# 51-2001-01-18_04_Power_Module_Schematic.net
KiCad netlist of a schematic drawn in Altium Designer
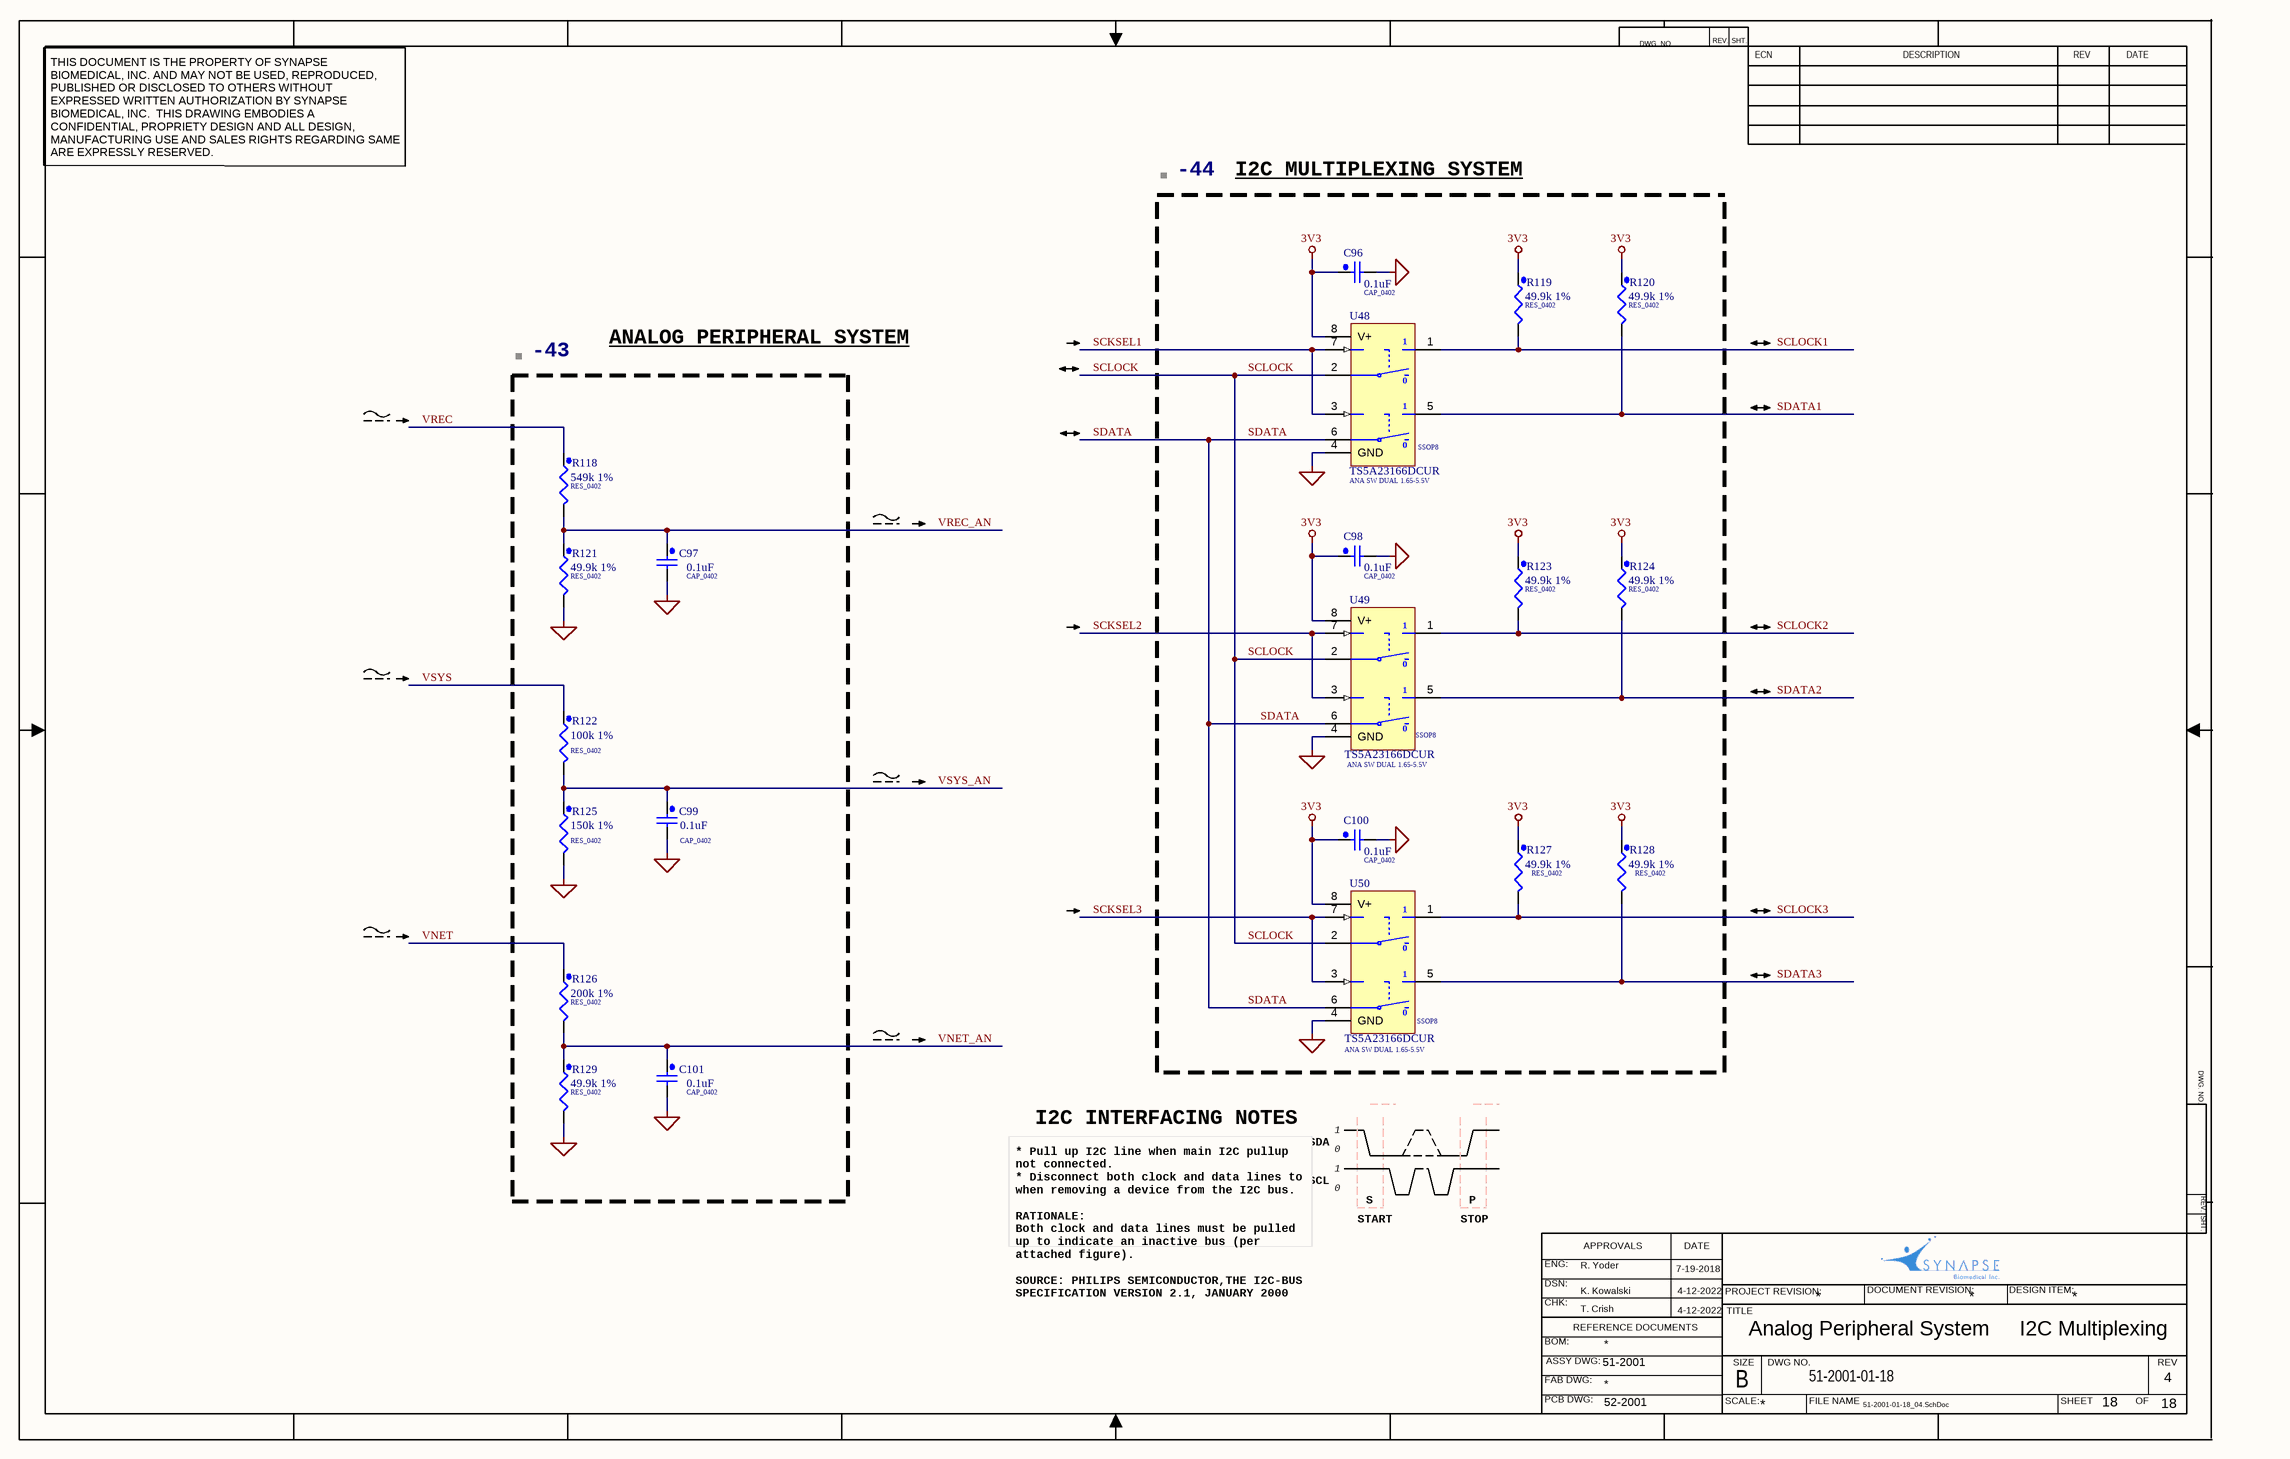
[diagram p0: 51-2001-01-18_04 Power Module Schematic.SchDoc]

(export (version "E")
  (design (tool "Eeschema 10.0.6"))
  (components
    (comp (ref "-43")
      (value "BOM_S1")
      (description "BOM item small graphic")
      (fields (field (name "XDESCRIPTION") "ANALOG PERIPHERAL SYSTEM"))
      (libsource (lib "BOM_sym") (part "BOM_S1"))
    )
    (comp (ref "-44")
      (value "BOM_S1")
      (description "BOM item small graphic")
      (fields (field (name "XDESCRIPTION") "I2C MULTIPLEXING SYSTEM"))
      (libsource (lib "BOM_sym") (part "BOM_S1"))
    )
    (comp (ref "C96")
      (value "0.1uF")
      (footprint "CAP_0402")
      (description "0.1uF, 16V, X7R, 0402, RoHS")
      (fields
        (field (name "MFR") "Murata")
        (field (name "PACKAGEDESCRIPTION") "CAP_0402")
        (field (name "MPN") "GRM155R71C104KA88D")
      )
      (libsource (lib "NNPS Integrated Parts") (part "GRM155R71C104KA88D"))
    )
    (comp (ref "C97")
      (value "0.1uF")
      (footprint "CAP_0402")
      (description "0.1uF, 16V, X7R, 0402, RoHS")
      (fields
        (field (name "MFR") "Murata")
        (field (name "PACKAGEDESCRIPTION") "CAP_0402")
        (field (name "MPN") "GRM155R71C104KA88D")
      )
      (libsource (lib "NNPS Integrated Parts") (part "GRM155R71C104KA88D"))
    )
    (comp (ref "C98")
      (value "0.1uF")
      (footprint "CAP_0402")
      (description "0.1uF, 16V, X7R, 0402, RoHS")
      (fields
        (field (name "MFR") "Murata")
        (field (name "PACKAGEDESCRIPTION") "CAP_0402")
        (field (name "MPN") "GRM155R71C104KA88D")
      )
      (libsource (lib "NNPS Integrated Parts") (part "GRM155R71C104KA88D"))
    )
    (comp (ref "C99")
      (value "0.1uF")
      (footprint "CAP_0402")
      (description "0.1uF, 16V, X7R, 0402, RoHS")
      (fields
        (field (name "MFR") "Murata")
        (field (name "PACKAGEDESCRIPTION") "CAP_0402")
        (field (name "MPN") "GRM155R71C104KA88D")
      )
      (libsource (lib "NNPS Integrated Parts") (part "GRM155R71C104KA88D"))
    )
    (comp (ref "C100")
      (value "0.1uF")
      (footprint "CAP_0402")
      (description "0.1uF, 16V, X7R, 0402, RoHS")
      (fields
        (field (name "MFR") "Murata")
        (field (name "PACKAGEDESCRIPTION") "CAP_0402")
        (field (name "MPN") "GRM155R71C104KA88D")
      )
      (libsource (lib "NNPS Integrated Parts") (part "GRM155R71C104KA88D"))
    )
    (comp (ref "C101")
      (value "0.1uF")
      (footprint "CAP_0402")
      (description "0.1uF, 16V, X7R, 0402, RoHS")
      (fields
        (field (name "MFR") "Murata")
        (field (name "PACKAGEDESCRIPTION") "CAP_0402")
        (field (name "MPN") "GRM155R71C104KA88D")
      )
      (libsource (lib "NNPS Integrated Parts") (part "GRM155R71C104KA88D"))
    )
    (comp (ref "R118")
      (value "549k 1%")
      (footprint "RES_0402")
      (description "549k ohm, 1%, 1/16W, 0402, RoHS")
      (fields
        (field (name "MFR") "Vishay")
        (field (name "PACKAGEDESCRIPTION") "RES_0402")
        (field (name "MPN") "CRCW0402549KFKED")
      )
      (libsource (lib "NNPS Integrated Parts") (part "CRCW0402549KFKED"))
    )
    (comp (ref "R119")
      (value "49.9k 1%")
      (footprint "RES_0402")
      (description "49.9k ohm, 1%, 1/16W, 0402, RoHS")
      (fields
        (field (name "MFR") "Vishay Dale")
        (field (name "PACKAGEDESCRIPTION") "RES_0402")
        (field (name "MPN") "CRCW040249K9FKED")
      )
      (libsource (lib "NNPS Integrated Parts") (part "MCR01MZPF4992"))
    )
    (comp (ref "R120")
      (value "49.9k 1%")
      (footprint "RES_0402")
      (description "49.9k ohm, 1%, 1/16W, 0402, RoHS")
      (fields
        (field (name "MFR") "Vishay Dale")
        (field (name "PACKAGEDESCRIPTION") "RES_0402")
        (field (name "MPN") "CRCW040249K9FKED")
      )
      (libsource (lib "NNPS Integrated Parts") (part "MCR01MZPF4992"))
    )
    (comp (ref "R121")
      (value "49.9k 1%")
      (footprint "RES_0402")
      (description "49.9k ohm, 1%, 1/16W, 0402, RoHS")
      (fields
        (field (name "MFR") "Vishay Dale")
        (field (name "PACKAGEDESCRIPTION") "RES_0402")
        (field (name "MPN") "CRCW040249K9FKED")
      )
      (libsource (lib "NNPS Integrated Parts") (part "MCR01MZPF4992"))
    )
    (comp (ref "R122")
      (value "100k 1%")
      (footprint "RES_0402")
      (description "100k ohm, 1%, 1/16W, smd, 0402, RoHS")
      (fields
        (field (name "MFR") "Vishay Dale")
        (field (name "PACKAGEDESCRIPTION") "RES_0402")
        (field (name "MPN") "CRCW0402100KFKED")
      )
      (libsource (lib "NNPS Integrated Parts") (part "MCR01MZPF1003"))
    )
    (comp (ref "R123")
      (value "49.9k 1%")
      (footprint "RES_0402")
      (description "49.9k ohm, 1%, 1/16W, 0402, RoHS")
      (fields
        (field (name "MFR") "Vishay Dale")
        (field (name "PACKAGEDESCRIPTION") "RES_0402")
        (field (name "MPN") "CRCW040249K9FKED")
      )
      (libsource (lib "NNPS Integrated Parts") (part "MCR01MZPF4992"))
    )
    (comp (ref "R124")
      (value "49.9k 1%")
      (footprint "RES_0402")
      (description "49.9k ohm, 1%, 1/16W, 0402, RoHS")
      (fields
        (field (name "MFR") "Vishay Dale")
        (field (name "PACKAGEDESCRIPTION") "RES_0402")
        (field (name "MPN") "CRCW040249K9FKED")
      )
      (libsource (lib "NNPS Integrated Parts") (part "MCR01MZPF4992"))
    )
    (comp (ref "R125")
      (value "150k 1%")
      (footprint "RES_0402")
      (description "150k ohm, 1%, 1/16W, smd, 0402, RoHS")
      (fields
        (field (name "MFR") "Vishay Dale")
        (field (name "PACKAGEDESCRIPTION") "RES_0402")
        (field (name "MPN") "CRCW0402150KFKED")
      )
      (libsource (lib "NNPS Integrated Parts") (part "MCR01MZPF1503"))
    )
    (comp (ref "R126")
      (value "200k 1%")
      (footprint "RES_0402")
      (description "200k ohm, 1%, 1/16W, 0402, RoHS")
      (fields
        (field (name "MFR") "Vishay Dale")
        (field (name "PACKAGEDESCRIPTION") "RES_0402")
        (field (name "MPN") "CRCW0402200KFKED")
      )
      (libsource (lib "NNPS Integrated Parts") (part "MCR01MZPF2003"))
    )
    (comp (ref "R127")
      (value "49.9k 1%")
      (footprint "RES_0402")
      (description "49.9k ohm, 1%, 1/16W, 0402, RoHS")
      (fields
        (field (name "MFR") "Vishay Dale")
        (field (name "PACKAGEDESCRIPTION") "RES_0402")
        (field (name "MPN") "CRCW040249K9FKED")
      )
      (libsource (lib "NNPS Integrated Parts") (part "MCR01MZPF4992"))
    )
    (comp (ref "R128")
      (value "49.9k 1%")
      (footprint "RES_0402")
      (description "49.9k ohm, 1%, 1/16W, 0402, RoHS")
      (fields
        (field (name "MFR") "Vishay Dale")
        (field (name "PACKAGEDESCRIPTION") "RES_0402")
        (field (name "MPN") "CRCW040249K9FKED")
      )
      (libsource (lib "NNPS Integrated Parts") (part "MCR01MZPF4992"))
    )
    (comp (ref "R129")
      (value "49.9k 1%")
      (footprint "RES_0402")
      (description "49.9k ohm, 1%, 1/16W, 0402, RoHS")
      (fields
        (field (name "MFR") "Vishay Dale")
        (field (name "PACKAGEDESCRIPTION") "RES_0402")
        (field (name "MPN") "CRCW040249K9FKED")
      )
      (libsource (lib "NNPS Integrated Parts") (part "MCR01MZPF4992"))
    )
    (comp (ref "U48")
      (value "ANA SW DUAL 1.65-5.5V")
      (footprint "VSSOP8")
      (description "Analog Switch, DUAL, 2-Channel, SSOP8, RoHS")
      (fields
        (field (name "PACKAGEDESCRIPTION") "SSOP8")
        (field (name "MFR") "Texas Instruments")
        (field (name "MPN") "TS5A23166DCUR")
      )
      (libsource (lib "NNPS Integrated Parts") (part "TS5A23166DCUR"))
    )
    (comp (ref "U49")
      (value "ANA SW DUAL 1.65-5.5V")
      (footprint "VSSOP8")
      (description "Analog Switch, DUAL, 2-Channel, SSOP8, RoHS")
      (fields
        (field (name "PACKAGEDESCRIPTION") "SSOP8")
        (field (name "MFR") "Texas Instruments")
        (field (name "MPN") "TS5A23166DCUR")
      )
      (libsource (lib "NNPS Integrated Parts") (part "TS5A23166DCUR"))
    )
    (comp (ref "U50")
      (value "ANA SW DUAL 1.65-5.5V")
      (footprint "VSSOP8")
      (description "Analog Switch, DUAL, 2-Channel, SSOP8, RoHS")
      (fields
        (field (name "PACKAGEDESCRIPTION") "SSOP8")
        (field (name "MFR") "Texas Instruments")
        (field (name "MPN") "TS5A23166DCUR")
      )
      (libsource (lib "NNPS Integrated Parts") (part "TS5A23166DCUR"))
    )
  )
  (nets
    (net (code "1") (name "/SCKSEL1") (class "Default")
      (node (ref "U48") (pin "3") (pinfunction "IN2_3") (pintype "input"))
      (node (ref "U48") (pin "7") (pinfunction "IN1_7") (pintype "input"))
    )
    (net (code "2") (name "/SCKSEL2") (class "Default")
      (node (ref "U49") (pin "3") (pinfunction "IN2_3") (pintype "input"))
      (node (ref "U49") (pin "7") (pinfunction "IN1_7") (pintype "input"))
    )
    (net (code "3") (name "/SCKSEL3") (class "Default")
      (node (ref "U50") (pin "3") (pinfunction "IN2_3") (pintype "input"))
      (node (ref "U50") (pin "7") (pinfunction "IN1_7") (pintype "input"))
    )
    (net (code "4") (name "/SCLOCK") (class "Default")
      (node (ref "U48") (pin "2") (pinfunction "COM1_2") (pintype "passive"))
      (node (ref "U49") (pin "2") (pinfunction "COM1_2") (pintype "passive"))
      (node (ref "U50") (pin "2") (pinfunction "COM1_2") (pintype "passive"))
    )
    (net (code "5") (name "/SCLOCK1") (class "Default")
      (node (ref "R119") (pin "2") (pinfunction "2_2") (pintype "passive"))
      (node (ref "U48") (pin "1") (pinfunction "NO1_1") (pintype "passive"))
    )
    (net (code "6") (name "/SCLOCK2") (class "Default")
      (node (ref "R123") (pin "2") (pinfunction "2_2") (pintype "passive"))
      (node (ref "U49") (pin "1") (pinfunction "NO1_1") (pintype "passive"))
    )
    (net (code "7") (name "/SCLOCK3") (class "Default")
      (node (ref "R127") (pin "2") (pinfunction "2_2") (pintype "passive"))
      (node (ref "U50") (pin "1") (pinfunction "NO1_1") (pintype "passive"))
    )
    (net (code "8") (name "/SDATA") (class "Default")
      (node (ref "U48") (pin "6") (pinfunction "COM2_6") (pintype "passive"))
      (node (ref "U49") (pin "6") (pinfunction "COM2_6") (pintype "passive"))
      (node (ref "U50") (pin "6") (pinfunction "COM2_6") (pintype "passive"))
    )
    (net (code "9") (name "/SDATA1") (class "Default")
      (node (ref "R120") (pin "2") (pinfunction "2_2") (pintype "passive"))
      (node (ref "U48") (pin "5") (pinfunction "NO2_5") (pintype "passive"))
    )
    (net (code "10") (name "/SDATA2") (class "Default")
      (node (ref "R124") (pin "2") (pinfunction "2_2") (pintype "passive"))
      (node (ref "U49") (pin "5") (pinfunction "NO2_5") (pintype "passive"))
    )
    (net (code "11") (name "/SDATA3") (class "Default")
      (node (ref "R128") (pin "2") (pinfunction "2_2") (pintype "passive"))
      (node (ref "U50") (pin "5") (pinfunction "NO2_5") (pintype "passive"))
    )
    (net (code "12") (name "/VNET") (class "Default")
      (node (ref "R126") (pin "1") (pinfunction "1_1") (pintype "passive"))
    )
    (net (code "13") (name "/VNET_AN") (class "Default")
      (node (ref "C101") (pin "1") (pinfunction "1_1") (pintype "passive"))
      (node (ref "R126") (pin "2") (pinfunction "2_2") (pintype "passive"))
      (node (ref "R129") (pin "1") (pinfunction "1_1") (pintype "passive"))
    )
    (net (code "14") (name "/VREC") (class "Default")
      (node (ref "R118") (pin "1") (pinfunction "1_1") (pintype "passive"))
    )
    (net (code "15") (name "/VREC_AN") (class "Default")
      (node (ref "C97") (pin "1") (pinfunction "1_1") (pintype "passive"))
      (node (ref "R118") (pin "2") (pinfunction "2_2") (pintype "passive"))
      (node (ref "R121") (pin "1") (pinfunction "1_1") (pintype "passive"))
    )
    (net (code "16") (name "/VSYS") (class "Default")
      (node (ref "R122") (pin "1") (pinfunction "1_1") (pintype "passive"))
    )
    (net (code "17") (name "/VSYS_AN") (class "Default")
      (node (ref "C99") (pin "1") (pinfunction "1_1") (pintype "passive"))
      (node (ref "R122") (pin "2") (pinfunction "2_2") (pintype "passive"))
      (node (ref "R125") (pin "1") (pinfunction "1_1") (pintype "passive"))
    )
    (net (code "18") (name "3V3") (class "Default")
      (node (ref "C100") (pin "1") (pinfunction "1_1") (pintype "passive"))
      (node (ref "C96") (pin "1") (pinfunction "1_1") (pintype "passive"))
      (node (ref "C98") (pin "1") (pinfunction "1_1") (pintype "passive"))
      (node (ref "R119") (pin "1") (pinfunction "1_1") (pintype "passive"))
      (node (ref "R120") (pin "1") (pinfunction "1_1") (pintype "passive"))
      (node (ref "R123") (pin "1") (pinfunction "1_1") (pintype "passive"))
      (node (ref "R124") (pin "1") (pinfunction "1_1") (pintype "passive"))
      (node (ref "R127") (pin "1") (pinfunction "1_1") (pintype "passive"))
      (node (ref "R128") (pin "1") (pinfunction "1_1") (pintype "passive"))
      (node (ref "U48") (pin "8") (pinfunction "V+_8") (pintype "power_in"))
      (node (ref "U49") (pin "8") (pinfunction "V+_8") (pintype "power_in"))
      (node (ref "U50") (pin "8") (pinfunction "V+_8") (pintype "power_in"))
    )
    (net (code "19") (name "GND") (class "Default")
      (node (ref "C100") (pin "2") (pinfunction "2_2") (pintype "passive"))
      (node (ref "C101") (pin "2") (pinfunction "2_2") (pintype "passive"))
      (node (ref "C96") (pin "2") (pinfunction "2_2") (pintype "passive"))
      (node (ref "C97") (pin "2") (pinfunction "2_2") (pintype "passive"))
      (node (ref "C98") (pin "2") (pinfunction "2_2") (pintype "passive"))
      (node (ref "C99") (pin "2") (pinfunction "2_2") (pintype "passive"))
      (node (ref "R121") (pin "2") (pinfunction "2_2") (pintype "passive"))
      (node (ref "R125") (pin "2") (pinfunction "2_2") (pintype "passive"))
      (node (ref "R129") (pin "2") (pinfunction "2_2") (pintype "passive"))
      (node (ref "U48") (pin "4") (pinfunction "GND_4") (pintype "power_in"))
      (node (ref "U49") (pin "4") (pinfunction "GND_4") (pintype "power_in"))
      (node (ref "U50") (pin "4") (pinfunction "GND_4") (pintype "power_in"))
    )
  )
)
